# V0_1.net
KiCad netlist of a schematic drawn in EAGLE
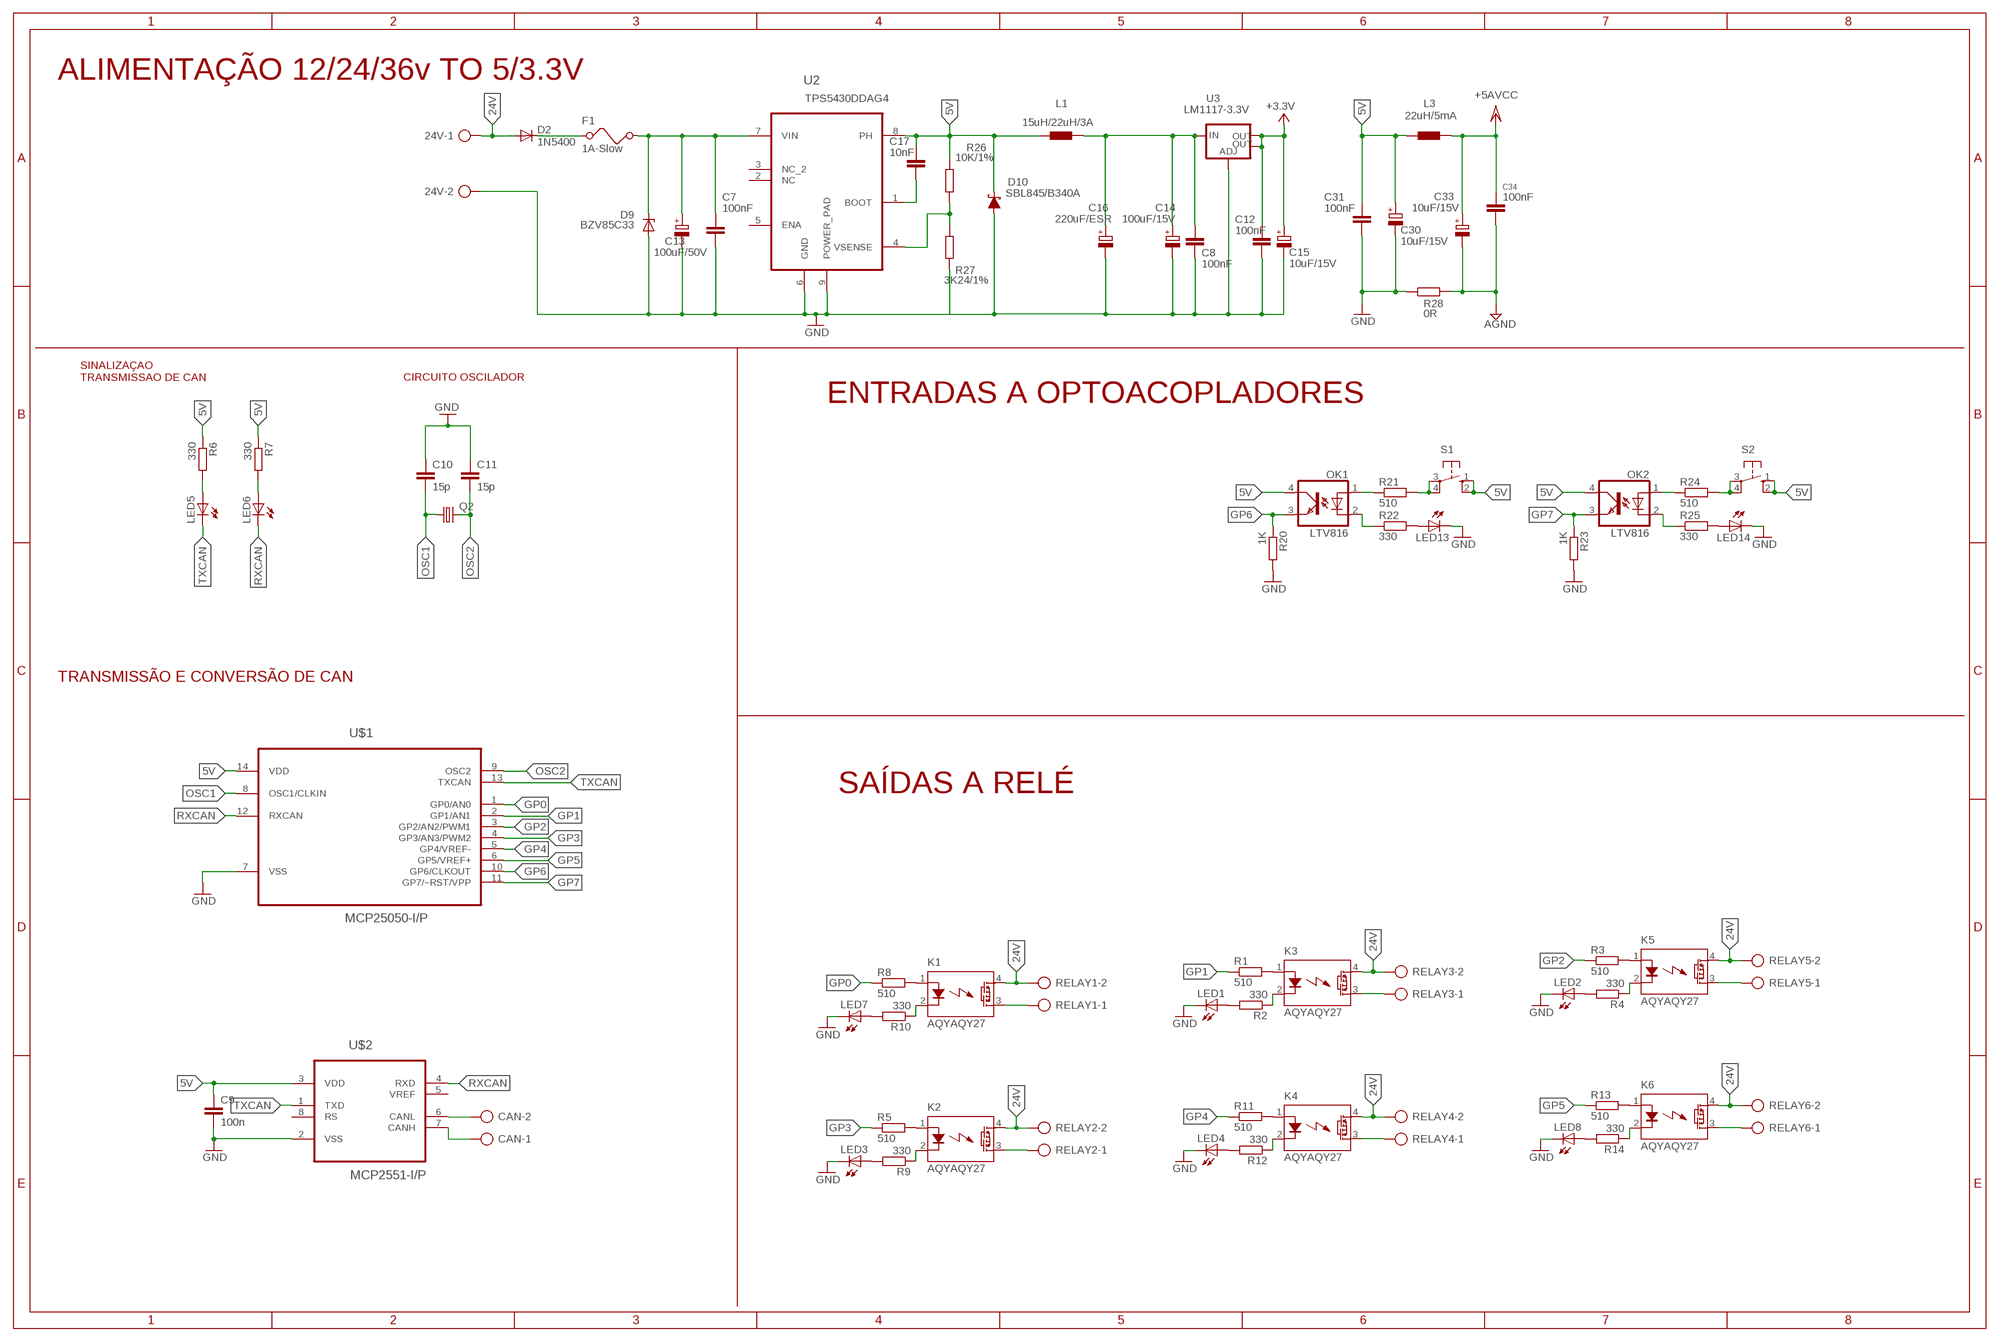
[diagram p0: schematic, sheet 1]

(export (version "E")
  (design (tool "Eeschema 10.0.6"))
  (components
    (comp (ref "24V")
      (value "AK300/2")
      (footprint "eagle-import:AK300_2")
      (libsource (lib "eagle-import") (part "AK300/2"))
    )
    (comp (ref "C7")
      (value "100nF")
      (footprint "eagle-import:C0805")
      (libsource (lib "eagle-import") (part "C-EUC0805"))
    )
    (comp (ref "C8")
      (value "100nF")
      (footprint "eagle-import:C0805")
      (libsource (lib "eagle-import") (part "C-EUC0805"))
    )
    (comp (ref "C9")
      (value "100n")
      (footprint "eagle-import:C050-025X075")
      (libsource (lib "eagle-import") (part "C-EU050-025X075"))
    )
    (comp (ref "C10")
      (value "15p")
      (footprint "eagle-import:C025-024X044")
      (libsource (lib "eagle-import") (part "C-EU025-024X044"))
    )
    (comp (ref "C11")
      (value "15p")
      (footprint "eagle-import:C025-024X044")
      (libsource (lib "eagle-import") (part "C-EU025-024X044"))
    )
    (comp (ref "C12")
      (value "100nF")
      (footprint "eagle-import:C0805")
      (libsource (lib "eagle-import") (part "C-EUC0805"))
    )
    (comp (ref "C13")
      (value "100uF/50V")
      (footprint "eagle-import:E5-10,5")
      (libsource (lib "eagle-import") (part "CPOL-EUE5-10.5"))
    )
    (comp (ref "C14")
      (value "100uF/15V")
      (footprint "eagle-import:E5-10,5")
      (libsource (lib "eagle-import") (part "CPOL-EUE5-10.5"))
    )
    (comp (ref "C15")
      (value "10uF/15V")
      (footprint "eagle-import:E5-10,5")
      (libsource (lib "eagle-import") (part "CPOL-EUE5-10.5"))
    )
    (comp (ref "C16")
      (value "220uF/ESR")
      (footprint "eagle-import:E5-10,5")
      (libsource (lib "eagle-import") (part "CPOL-EUE5-10.5"))
    )
    (comp (ref "C17")
      (value "10nF")
      (footprint "eagle-import:C0805")
      (libsource (lib "eagle-import") (part "C-EUC0805"))
    )
    (comp (ref "C30")
      (value "10uF/15V")
      (footprint "eagle-import:E5-10,5")
      (libsource (lib "eagle-import") (part "CPOL-EUE5-10.5"))
    )
    (comp (ref "C31")
      (value "100nF")
      (footprint "eagle-import:C0805")
      (libsource (lib "eagle-import") (part "C-EUC0805"))
    )
    (comp (ref "C33")
      (value "10uF/15V")
      (footprint "eagle-import:E5-10,5")
      (libsource (lib "eagle-import") (part "CPOL-EUE5-10.5"))
    )
    (comp (ref "C34")
      (value "100nF")
      (footprint "eagle-import:C0805")
      (libsource (lib "eagle-import") (part "C-EUC0805"))
    )
    (comp (ref "CAN")
      (value "AK300/2")
      (footprint "eagle-import:AK300_2")
      (libsource (lib "eagle-import") (part "AK300/2"))
    )
    (comp (ref "D2")
      (value "1N5400")
      (footprint "eagle-import:DO201-15")
      (libsource (lib "eagle-import") (part "1N5400"))
    )
    (comp (ref "D9")
      (value "BZV85C33")
      (footprint "eagle-import:F126Z10")
      (libsource (lib "eagle-import") (part "ZENER-DIODEF126-10"))
    )
    (comp (ref "D10")
      (value "SBL845/B340A")
      (footprint "eagle-import:SMA-DIODE")
      (libsource (lib "eagle-import") (part "DIODE-SCHOTTKY-B340A"))
    )
    (comp (ref "F1")
      (value "1A-Slow")
      (footprint "eagle-import:FUSE")
      (libsource (lib "eagle-import") (part "FUSE"))
    )
    (comp (ref "K1")
      (value "AQYAQY27")
      (footprint "eagle-import:AQY27")
      (libsource (lib "eagle-import") (part "AQYAQY27"))
    )
    (comp (ref "K2")
      (value "AQYAQY27")
      (footprint "eagle-import:AQY27")
      (libsource (lib "eagle-import") (part "AQYAQY27"))
    )
    (comp (ref "K3")
      (value "AQYAQY27")
      (footprint "eagle-import:AQY27")
      (libsource (lib "eagle-import") (part "AQYAQY27"))
    )
    (comp (ref "K4")
      (value "AQYAQY27")
      (footprint "eagle-import:AQY27")
      (libsource (lib "eagle-import") (part "AQYAQY27"))
    )
    (comp (ref "K5")
      (value "AQYAQY27")
      (footprint "eagle-import:AQY27")
      (libsource (lib "eagle-import") (part "AQYAQY27"))
    )
    (comp (ref "K6")
      (value "AQYAQY27")
      (footprint "eagle-import:AQY27")
      (libsource (lib "eagle-import") (part "AQYAQY27"))
    )
    (comp (ref "L1")
      (value "15uH/22uH/3A")
      (footprint "eagle-import:DR1030")
      (libsource (lib "eagle-import") (part "DR1030"))
    )
    (comp (ref "L3")
      (value "22uH/5mA")
      (footprint "eagle-import:BL01RN1A")
      (libsource (lib "eagle-import") (part "BL01RN1A"))
    )
    (comp (ref "LED1")
      (value "LED3MM")
      (footprint "eagle-import:LED3MM")
      (libsource (lib "eagle-import") (part "LED3MM"))
    )
    (comp (ref "LED2")
      (value "LED3MM")
      (footprint "eagle-import:LED3MM")
      (libsource (lib "eagle-import") (part "LED3MM"))
    )
    (comp (ref "LED3")
      (value "LED3MM")
      (footprint "eagle-import:LED3MM")
      (libsource (lib "eagle-import") (part "LED3MM"))
    )
    (comp (ref "LED4")
      (value "LED3MM")
      (footprint "eagle-import:LED3MM")
      (libsource (lib "eagle-import") (part "LED3MM"))
    )
    (comp (ref "LED5")
      (value "LED3MM")
      (footprint "eagle-import:LED3MM")
      (libsource (lib "eagle-import") (part "LED3MM"))
    )
    (comp (ref "LED6")
      (value "LED3MM")
      (footprint "eagle-import:LED3MM")
      (libsource (lib "eagle-import") (part "LED3MM"))
    )
    (comp (ref "LED7")
      (value "LED3MM")
      (footprint "eagle-import:LED3MM")
      (libsource (lib "eagle-import") (part "LED3MM"))
    )
    (comp (ref "LED8")
      (value "LED3MM")
      (footprint "eagle-import:LED3MM")
      (libsource (lib "eagle-import") (part "LED3MM"))
    )
    (comp (ref "LED13")
      (value "LED3MM")
      (footprint "eagle-import:LED3MM")
      (libsource (lib "eagle-import") (part "LED3MM"))
    )
    (comp (ref "LED14")
      (value "LED3MM")
      (footprint "eagle-import:LED3MM")
      (libsource (lib "eagle-import") (part "LED3MM"))
    )
    (comp (ref "OK1")
      (value "LTV816")
      (footprint "eagle-import:DIL04")
      (libsource (lib "eagle-import") (part "LTV816"))
    )
    (comp (ref "OK2")
      (value "LTV816")
      (footprint "eagle-import:DIL04")
      (libsource (lib "eagle-import") (part "LTV816"))
    )
    (comp (ref "Q2")
      (value "CRYSTALHC49S")
      (footprint "eagle-import:HC49_S")
      (libsource (lib "eagle-import") (part "CRYSTALHC49S"))
    )
    (comp (ref "R1")
      (value "510")
      (footprint "eagle-import:0204_5")
      (libsource (lib "eagle-import") (part "R-EU_0204/5"))
    )
    (comp (ref "R2")
      (value "330")
      (footprint "eagle-import:0204_5")
      (libsource (lib "eagle-import") (part "R-EU_0204/5"))
    )
    (comp (ref "R3")
      (value "510")
      (footprint "eagle-import:0204_5")
      (libsource (lib "eagle-import") (part "R-EU_0204/5"))
    )
    (comp (ref "R4")
      (value "330")
      (footprint "eagle-import:0204_5")
      (libsource (lib "eagle-import") (part "R-EU_0204/5"))
    )
    (comp (ref "R5")
      (value "510")
      (footprint "eagle-import:0204_5")
      (libsource (lib "eagle-import") (part "R-EU_0204/5"))
    )
    (comp (ref "R6")
      (value "330")
      (footprint "eagle-import:0204_5")
      (libsource (lib "eagle-import") (part "R-EU_0204/5"))
    )
    (comp (ref "R7")
      (value "330")
      (footprint "eagle-import:0204_5")
      (libsource (lib "eagle-import") (part "R-EU_0204/5"))
    )
    (comp (ref "R8")
      (value "510")
      (footprint "eagle-import:0204_5")
      (libsource (lib "eagle-import") (part "R-EU_0204/5"))
    )
    (comp (ref "R9")
      (value "330")
      (footprint "eagle-import:0204_5")
      (libsource (lib "eagle-import") (part "R-EU_0204/5"))
    )
    (comp (ref "R10")
      (value "330")
      (footprint "eagle-import:0204_5")
      (libsource (lib "eagle-import") (part "R-EU_0204/5"))
    )
    (comp (ref "R11")
      (value "510")
      (footprint "eagle-import:0204_5")
      (libsource (lib "eagle-import") (part "R-EU_0204/5"))
    )
    (comp (ref "R12")
      (value "330")
      (footprint "eagle-import:0204_5")
      (libsource (lib "eagle-import") (part "R-EU_0204/5"))
    )
    (comp (ref "R13")
      (value "510")
      (footprint "eagle-import:0204_5")
      (libsource (lib "eagle-import") (part "R-EU_0204/5"))
    )
    (comp (ref "R14")
      (value "330")
      (footprint "eagle-import:0204_5")
      (libsource (lib "eagle-import") (part "R-EU_0204/5"))
    )
    (comp (ref "R20")
      (value "1K")
      (footprint "eagle-import:0204_5")
      (libsource (lib "eagle-import") (part "R-EU_0204/5"))
    )
    (comp (ref "R21")
      (value "510")
      (footprint "eagle-import:0204_5")
      (libsource (lib "eagle-import") (part "R-EU_0204/5"))
    )
    (comp (ref "R22")
      (value "330")
      (footprint "eagle-import:0204_5")
      (libsource (lib "eagle-import") (part "R-EU_0204/5"))
    )
    (comp (ref "R23")
      (value "1K")
      (footprint "eagle-import:0204_5")
      (libsource (lib "eagle-import") (part "R-EU_0204/5"))
    )
    (comp (ref "R24")
      (value "510")
      (footprint "eagle-import:0204_5")
      (libsource (lib "eagle-import") (part "R-EU_0204/5"))
    )
    (comp (ref "R25")
      (value "330")
      (footprint "eagle-import:0204_5")
      (libsource (lib "eagle-import") (part "R-EU_0204/5"))
    )
    (comp (ref "R26")
      (value "10K/1%")
      (footprint "eagle-import:R0603")
      (libsource (lib "eagle-import") (part "R-EU_R0603"))
    )
    (comp (ref "R27")
      (value "3K24/1%")
      (footprint "eagle-import:R0603")
      (libsource (lib "eagle-import") (part "R-EU_R0603"))
    )
    (comp (ref "R28")
      (value "0R")
      (footprint "eagle-import:R0603")
      (libsource (lib "eagle-import") (part "R-EU_R0603"))
    )
    (comp (ref "RELAY1")
      (value "AK300/2")
      (footprint "eagle-import:AK300_2")
      (libsource (lib "eagle-import") (part "AK300/2"))
    )
    (comp (ref "RELAY2")
      (value "AK300/2")
      (footprint "eagle-import:AK300_2")
      (libsource (lib "eagle-import") (part "AK300/2"))
    )
    (comp (ref "RELAY3")
      (value "AK300/2")
      (footprint "eagle-import:AK300_2")
      (libsource (lib "eagle-import") (part "AK300/2"))
    )
    (comp (ref "RELAY4")
      (value "AK300/2")
      (footprint "eagle-import:AK300_2")
      (libsource (lib "eagle-import") (part "AK300/2"))
    )
    (comp (ref "RELAY5")
      (value "AK300/2")
      (footprint "eagle-import:AK300_2")
      (libsource (lib "eagle-import") (part "AK300/2"))
    )
    (comp (ref "RELAY6")
      (value "AK300/2")
      (footprint "eagle-import:AK300_2")
      (libsource (lib "eagle-import") (part "AK300/2"))
    )
    (comp (ref "S1")
      (value "10-XX")
      (footprint "eagle-import:B3F-10XX")
      (fields (field (name "MPN") "B3F-1000"))
      (libsource (lib "eagle-import") (part "10-XX"))
    )
    (comp (ref "S2")
      (value "10-XX")
      (footprint "eagle-import:B3F-10XX")
      (fields (field (name "MPN") "B3F-1000"))
      (libsource (lib "eagle-import") (part "10-XX"))
    )
    (comp (ref "U$1")
      (value "MCP25050-I/P")
      (footprint "eagle-import:DIP254P762X432-14")
      (libsource (lib "eagle-import") (part "MCP25050-I/P"))
    )
    (comp (ref "U$2")
      (value "MCP2551-I/P")
      (footprint "eagle-import:DIP254P762X432-8")
      (libsource (lib "eagle-import") (part "MCP2551-I/P"))
    )
    (comp (ref "U2")
      (value "TPS5430DDAG4")
      (footprint "eagle-import:SOIC127P600X170-9N")
      (fields (field (name "MPN") "TPS5430DDAG4"))
      (libsource (lib "eagle-import") (part "TPS5430DDAG4"))
    )
    (comp (ref "U3")
      (value "LM1117-3.3V")
      (footprint "eagle-import:SOT223")
      (libsource (lib "eagle-import") (part "V_REG_LM1117SOT223"))
    )
  )
  (nets
    (net (code "1") (name "+3.3V") (class "Default")
      (node (ref "C12") (pin "1") (pinfunction "1_1") (pintype "passive"))
      (node (ref "C15") (pin "+") (pinfunction "+_+") (pintype "passive"))
      (node (ref "U3") (pin "2") (pinfunction "OUT_2") (pintype "output"))
      (node (ref "U3") (pin "4") (pinfunction "OUT_4") (pintype "output"))
    )
    (net (code "2") (name "+5AVCC") (class "Default")
      (node (ref "C33") (pin "+") (pinfunction "+_+") (pintype "passive"))
      (node (ref "C34") (pin "1") (pinfunction "1_1") (pintype "passive"))
      (node (ref "L3") (pin "2") (pinfunction "2_2") (pintype "passive"))
    )
    (net (code "3") (name "5V") (class "Default")
      (node (ref "C17") (pin "1") (pinfunction "1_1") (pintype "passive"))
      (node (ref "C30") (pin "+") (pinfunction "+_+") (pintype "passive"))
      (node (ref "C31") (pin "1") (pinfunction "1_1") (pintype "passive"))
      (node (ref "C9") (pin "1") (pinfunction "1_1") (pintype "passive"))
      (node (ref "D10") (pin "C") (pinfunction "C_C") (pintype "passive"))
      (node (ref "L1") (pin "1") (pinfunction "1_1") (pintype "passive"))
      (node (ref "L3") (pin "1") (pinfunction "1_1") (pintype "passive"))
      (node (ref "OK1") (pin "4") (pinfunction "COL_4") (pintype "passive"))
      (node (ref "OK2") (pin "4") (pinfunction "COL_4") (pintype "passive"))
      (node (ref "R26") (pin "1") (pinfunction "1_1") (pintype "passive"))
      (node (ref "R6") (pin "1") (pinfunction "1_1") (pintype "passive"))
      (node (ref "R7") (pin "1") (pinfunction "1_1") (pintype "passive"))
      (node (ref "S1") (pin "1") (pinfunction "S_1") (pintype "passive"))
      (node (ref "S1") (pin "2") (pinfunction "S1_2") (pintype "passive"))
      (node (ref "S2") (pin "1") (pinfunction "S_1") (pintype "passive"))
      (node (ref "S2") (pin "2") (pinfunction "S1_2") (pintype "passive"))
      (node (ref "U$1") (pin "14") (pinfunction "VDD_14") (pintype "power_in"))
      (node (ref "U$2") (pin "3") (pinfunction "VDD_3") (pintype "power_in"))
      (node (ref "U2") (pin "8") (pinfunction "PH_8") (pintype "input"))
    )
    (net (code "4") (name "24V") (class "Default")
      (node (ref "24V") (pin "1") (pinfunction "KL_1") (pintype "passive"))
      (node (ref "D2") (pin "A") (pinfunction "A_A") (pintype "passive"))
      (node (ref "K1") (pin "4") (pinfunction "DS1_4") (pintype "passive"))
      (node (ref "K2") (pin "4") (pinfunction "DS1_4") (pintype "passive"))
      (node (ref "K3") (pin "4") (pinfunction "DS1_4") (pintype "passive"))
      (node (ref "K4") (pin "4") (pinfunction "DS1_4") (pintype "passive"))
      (node (ref "K5") (pin "4") (pinfunction "DS1_4") (pintype "passive"))
      (node (ref "K6") (pin "4") (pinfunction "DS1_4") (pintype "passive"))
      (node (ref "RELAY1") (pin "2") (pinfunction "KL_2") (pintype "passive"))
      (node (ref "RELAY2") (pin "2") (pinfunction "KL_2") (pintype "passive"))
      (node (ref "RELAY3") (pin "2") (pinfunction "KL_2") (pintype "passive"))
      (node (ref "RELAY4") (pin "2") (pinfunction "KL_2") (pintype "passive"))
      (node (ref "RELAY5") (pin "2") (pinfunction "KL_2") (pintype "passive"))
      (node (ref "RELAY6") (pin "2") (pinfunction "KL_2") (pintype "passive"))
    )
    (net (code "5") (name "AGND") (class "Default")
      (node (ref "C33") (pin "-") (pinfunction "-_-") (pintype "passive"))
      (node (ref "C34") (pin "2") (pinfunction "2_2") (pintype "passive"))
      (node (ref "R28") (pin "2") (pinfunction "2_2") (pintype "passive"))
    )
    (net (code "6") (name "GND") (class "Default")
      (node (ref "24V") (pin "2") (pinfunction "KL_2") (pintype "passive"))
      (node (ref "C10") (pin "1") (pinfunction "1_1") (pintype "passive"))
      (node (ref "C11") (pin "1") (pinfunction "1_1") (pintype "passive"))
      (node (ref "C12") (pin "2") (pinfunction "2_2") (pintype "passive"))
      (node (ref "C13") (pin "-") (pinfunction "-_-") (pintype "passive"))
      (node (ref "C14") (pin "-") (pinfunction "-_-") (pintype "passive"))
      (node (ref "C15") (pin "-") (pinfunction "-_-") (pintype "passive"))
      (node (ref "C16") (pin "-") (pinfunction "-_-") (pintype "passive"))
      (node (ref "C30") (pin "-") (pinfunction "-_-") (pintype "passive"))
      (node (ref "C31") (pin "2") (pinfunction "2_2") (pintype "passive"))
      (node (ref "C7") (pin "2") (pinfunction "2_2") (pintype "passive"))
      (node (ref "C8") (pin "2") (pinfunction "2_2") (pintype "passive"))
      (node (ref "C9") (pin "2") (pinfunction "2_2") (pintype "passive"))
      (node (ref "D10") (pin "A") (pinfunction "A_A") (pintype "passive"))
      (node (ref "D9") (pin "A") (pinfunction "A_A") (pintype "passive"))
      (node (ref "LED1") (pin "K") (pinfunction "C_K") (pintype "passive"))
      (node (ref "LED13") (pin "K") (pinfunction "C_K") (pintype "passive"))
      (node (ref "LED14") (pin "K") (pinfunction "C_K") (pintype "passive"))
      (node (ref "LED2") (pin "K") (pinfunction "C_K") (pintype "passive"))
      (node (ref "LED3") (pin "K") (pinfunction "C_K") (pintype "passive"))
      (node (ref "LED4") (pin "K") (pinfunction "C_K") (pintype "passive"))
      (node (ref "LED7") (pin "K") (pinfunction "C_K") (pintype "passive"))
      (node (ref "LED8") (pin "K") (pinfunction "C_K") (pintype "passive"))
      (node (ref "R20") (pin "2") (pinfunction "2_2") (pintype "passive"))
      (node (ref "R23") (pin "2") (pinfunction "2_2") (pintype "passive"))
      (node (ref "R27") (pin "2") (pinfunction "2_2") (pintype "passive"))
      (node (ref "R28") (pin "1") (pinfunction "1_1") (pintype "passive"))
      (node (ref "U$1") (pin "7") (pinfunction "VSS_7") (pintype "passive"))
      (node (ref "U$2") (pin "2") (pinfunction "VSS_2") (pintype "power_in"))
      (node (ref "U2") (pin "6") (pinfunction "GND_6") (pintype "passive"))
      (node (ref "U2") (pin "9") (pinfunction "POWER_PAD_9") (pintype "passive"))
      (node (ref "U3") (pin "1") (pinfunction "ADJ_1") (pintype "input"))
    )
    (net (code "7") (name "GP0") (class "Default")
      (node (ref "R8") (pin "1") (pinfunction "1_1") (pintype "passive"))
      (node (ref "U$1") (pin "1") (pinfunction "GP0/AN0_1") (pintype "bidirectional"))
    )
    (net (code "8") (name "GP1") (class "Default")
      (node (ref "R1") (pin "1") (pinfunction "1_1") (pintype "passive"))
      (node (ref "U$1") (pin "2") (pinfunction "GP1/AN1_2") (pintype "bidirectional"))
    )
    (net (code "9") (name "GP2") (class "Default")
      (node (ref "R3") (pin "1") (pinfunction "1_1") (pintype "passive"))
      (node (ref "U$1") (pin "3") (pinfunction "GP2/AN2/PWM1_3") (pintype "bidirectional"))
    )
    (net (code "10") (name "GP3") (class "Default")
      (node (ref "R5") (pin "1") (pinfunction "1_1") (pintype "passive"))
      (node (ref "U$1") (pin "4") (pinfunction "GP3/AN3/PWM2_4") (pintype "bidirectional"))
    )
    (net (code "11") (name "GP4") (class "Default")
      (node (ref "R11") (pin "1") (pinfunction "1_1") (pintype "passive"))
      (node (ref "U$1") (pin "5") (pinfunction "GP4/VREF-_5") (pintype "bidirectional"))
    )
    (net (code "12") (name "GP5") (class "Default")
      (node (ref "R13") (pin "1") (pinfunction "1_1") (pintype "passive"))
      (node (ref "U$1") (pin "6") (pinfunction "GP5/VREF+_6") (pintype "bidirectional"))
    )
    (net (code "13") (name "GP6") (class "Default")
      (node (ref "OK1") (pin "3") (pinfunction "EMIT_3") (pintype "passive"))
      (node (ref "R20") (pin "1") (pinfunction "1_1") (pintype "passive"))
      (node (ref "U$1") (pin "10") (pinfunction "GP6/CLKOUT_10") (pintype "bidirectional"))
    )
    (net (code "14") (name "GP7") (class "Default")
      (node (ref "OK2") (pin "3") (pinfunction "EMIT_3") (pintype "passive"))
      (node (ref "R23") (pin "1") (pinfunction "1_1") (pintype "passive"))
      (node (ref "U$1") (pin "11") (pinfunction "GP7/~{RST/VPP}_11") (pintype "bidirectional"))
    )
    (net (code "15") (name "Net-(CANA-KL)") (class "Default")
      (node (ref "CAN") (pin "1") (pinfunction "KL_1") (pintype "passive"))
      (node (ref "U$2") (pin "7") (pinfunction "CANH_7") (pintype "bidirectional"))
    )
    (net (code "16") (name "Net-(CANB-KL)") (class "Default")
      (node (ref "CAN") (pin "2") (pinfunction "KL_2") (pintype "passive"))
      (node (ref "U$2") (pin "6") (pinfunction "CANL_6") (pintype "bidirectional"))
    )
    (net (code "17") (name "Net-(D2-PadC)") (class "Default")
      (node (ref "D2") (pin "C") (pinfunction "C_C") (pintype "passive"))
      (node (ref "F1") (pin "1") (pinfunction "1_1") (pintype "passive"))
    )
    (net (code "18") (name "Net-(K1-A)") (class "Default")
      (node (ref "K1") (pin "1") (pinfunction "A_1") (pintype "passive"))
      (node (ref "R8") (pin "2") (pinfunction "2_2") (pintype "passive"))
    )
    (net (code "19") (name "Net-(K1-DS2)") (class "Default")
      (node (ref "K1") (pin "3") (pinfunction "DS2_3") (pintype "passive"))
      (node (ref "RELAY1") (pin "1") (pinfunction "KL_1") (pintype "passive"))
    )
    (net (code "20") (name "Net-(K1-K)") (class "Default")
      (node (ref "K1") (pin "2") (pinfunction "K_2") (pintype "passive"))
      (node (ref "R10") (pin "1") (pinfunction "1_1") (pintype "passive"))
    )
    (net (code "21") (name "Net-(K2-A)") (class "Default")
      (node (ref "K2") (pin "1") (pinfunction "A_1") (pintype "passive"))
      (node (ref "R5") (pin "2") (pinfunction "2_2") (pintype "passive"))
    )
    (net (code "22") (name "Net-(K2-DS2)") (class "Default")
      (node (ref "K2") (pin "3") (pinfunction "DS2_3") (pintype "passive"))
      (node (ref "RELAY2") (pin "1") (pinfunction "KL_1") (pintype "passive"))
    )
    (net (code "23") (name "Net-(K2-K)") (class "Default")
      (node (ref "K2") (pin "2") (pinfunction "K_2") (pintype "passive"))
      (node (ref "R9") (pin "1") (pinfunction "1_1") (pintype "passive"))
    )
    (net (code "24") (name "Net-(K3-A)") (class "Default")
      (node (ref "K3") (pin "1") (pinfunction "A_1") (pintype "passive"))
      (node (ref "R1") (pin "2") (pinfunction "2_2") (pintype "passive"))
    )
    (net (code "25") (name "Net-(K3-DS2)") (class "Default")
      (node (ref "K3") (pin "3") (pinfunction "DS2_3") (pintype "passive"))
      (node (ref "RELAY3") (pin "1") (pinfunction "KL_1") (pintype "passive"))
    )
    (net (code "26") (name "Net-(K3-K)") (class "Default")
      (node (ref "K3") (pin "2") (pinfunction "K_2") (pintype "passive"))
      (node (ref "R2") (pin "1") (pinfunction "1_1") (pintype "passive"))
    )
    (net (code "27") (name "Net-(K4-A)") (class "Default")
      (node (ref "K4") (pin "1") (pinfunction "A_1") (pintype "passive"))
      (node (ref "R11") (pin "2") (pinfunction "2_2") (pintype "passive"))
    )
    (net (code "28") (name "Net-(K4-DS2)") (class "Default")
      (node (ref "K4") (pin "3") (pinfunction "DS2_3") (pintype "passive"))
      (node (ref "RELAY4") (pin "1") (pinfunction "KL_1") (pintype "passive"))
    )
    (net (code "29") (name "Net-(K4-K)") (class "Default")
      (node (ref "K4") (pin "2") (pinfunction "K_2") (pintype "passive"))
      (node (ref "R12") (pin "1") (pinfunction "1_1") (pintype "passive"))
    )
    (net (code "30") (name "Net-(K5-A)") (class "Default")
      (node (ref "K5") (pin "1") (pinfunction "A_1") (pintype "passive"))
      (node (ref "R3") (pin "2") (pinfunction "2_2") (pintype "passive"))
    )
    (net (code "31") (name "Net-(K5-DS2)") (class "Default")
      (node (ref "K5") (pin "3") (pinfunction "DS2_3") (pintype "passive"))
      (node (ref "RELAY5") (pin "1") (pinfunction "KL_1") (pintype "passive"))
    )
    (net (code "32") (name "Net-(K5-K)") (class "Default")
      (node (ref "K5") (pin "2") (pinfunction "K_2") (pintype "passive"))
      (node (ref "R4") (pin "1") (pinfunction "1_1") (pintype "passive"))
    )
    (net (code "33") (name "Net-(K6-A)") (class "Default")
      (node (ref "K6") (pin "1") (pinfunction "A_1") (pintype "passive"))
      (node (ref "R13") (pin "2") (pinfunction "2_2") (pintype "passive"))
    )
    (net (code "34") (name "Net-(K6-DS2)") (class "Default")
      (node (ref "K6") (pin "3") (pinfunction "DS2_3") (pintype "passive"))
      (node (ref "RELAY6") (pin "1") (pinfunction "KL_1") (pintype "passive"))
    )
    (net (code "35") (name "Net-(K6-K)") (class "Default")
      (node (ref "K6") (pin "2") (pinfunction "K_2") (pintype "passive"))
      (node (ref "R14") (pin "1") (pinfunction "1_1") (pintype "passive"))
    )
    (net (code "36") (name "Net-(LED1-PadA)") (class "Default")
      (node (ref "LED1") (pin "A") (pinfunction "A_A") (pintype "passive"))
      (node (ref "R2") (pin "2") (pinfunction "2_2") (pintype "passive"))
    )
    (net (code "37") (name "Net-(LED2-PadA)") (class "Default")
      (node (ref "LED2") (pin "A") (pinfunction "A_A") (pintype "passive"))
      (node (ref "R4") (pin "2") (pinfunction "2_2") (pintype "passive"))
    )
    (net (code "38") (name "Net-(LED3-PadA)") (class "Default")
      (node (ref "LED3") (pin "A") (pinfunction "A_A") (pintype "passive"))
      (node (ref "R9") (pin "2") (pinfunction "2_2") (pintype "passive"))
    )
    (net (code "39") (name "Net-(LED4-PadA)") (class "Default")
      (node (ref "LED4") (pin "A") (pinfunction "A_A") (pintype "passive"))
      (node (ref "R12") (pin "2") (pinfunction "2_2") (pintype "passive"))
    )
    (net (code "40") (name "Net-(LED5-PadA)") (class "Default")
      (node (ref "LED5") (pin "A") (pinfunction "A_A") (pintype "passive"))
      (node (ref "R6") (pin "2") (pinfunction "2_2") (pintype "passive"))
    )
    (net (code "41") (name "Net-(LED6-PadA)") (class "Default")
      (node (ref "LED6") (pin "A") (pinfunction "A_A") (pintype "passive"))
      (node (ref "R7") (pin "2") (pinfunction "2_2") (pintype "passive"))
    )
    (net (code "42") (name "Net-(LED7-PadA)") (class "Default")
      (node (ref "LED7") (pin "A") (pinfunction "A_A") (pintype "passive"))
      (node (ref "R10") (pin "2") (pinfunction "2_2") (pintype "passive"))
    )
    (net (code "43") (name "Net-(LED8-PadA)") (class "Default")
      (node (ref "LED8") (pin "A") (pinfunction "A_A") (pintype "passive"))
      (node (ref "R14") (pin "2") (pinfunction "2_2") (pintype "passive"))
    )
    (net (code "44") (name "Net-(LED13-PadA)") (class "Default")
      (node (ref "LED13") (pin "A") (pinfunction "A_A") (pintype "passive"))
      (node (ref "R22") (pin "2") (pinfunction "2_2") (pintype "passive"))
    )
    (net (code "45") (name "Net-(LED14-PadA)") (class "Default")
      (node (ref "LED14") (pin "A") (pinfunction "A_A") (pintype "passive"))
      (node (ref "R25") (pin "2") (pinfunction "2_2") (pintype "passive"))
    )
    (net (code "46") (name "Net-(OK1-A)") (class "Default")
      (node (ref "OK1") (pin "1") (pinfunction "A_1") (pintype "passive"))
      (node (ref "R21") (pin "1") (pinfunction "1_1") (pintype "passive"))
    )
    (net (code "47") (name "Net-(OK1-C)") (class "Default")
      (node (ref "OK1") (pin "2") (pinfunction "C_2") (pintype "passive"))
      (node (ref "R22") (pin "1") (pinfunction "1_1") (pintype "passive"))
    )
    (net (code "48") (name "Net-(OK2-A)") (class "Default")
      (node (ref "OK2") (pin "1") (pinfunction "A_1") (pintype "passive"))
      (node (ref "R24") (pin "1") (pinfunction "1_1") (pintype "passive"))
    )
    (net (code "49") (name "Net-(OK2-C)") (class "Default")
      (node (ref "OK2") (pin "2") (pinfunction "C_2") (pintype "passive"))
      (node (ref "R25") (pin "1") (pinfunction "1_1") (pintype "passive"))
    )
    (net (code "50") (name "Net-(S1-P)") (class "Default")
      (node (ref "R21") (pin "2") (pinfunction "2_2") (pintype "passive"))
      (node (ref "S1") (pin "3") (pinfunction "P_3") (pintype "passive"))
      (node (ref "S1") (pin "4") (pinfunction "P1_4") (pintype "passive"))
    )
    (net (code "51") (name "Net-(S2-P)") (class "Default")
      (node (ref "R24") (pin "2") (pinfunction "2_2") (pintype "passive"))
      (node (ref "S2") (pin "3") (pinfunction "P_3") (pintype "passive"))
      (node (ref "S2") (pin "4") (pinfunction "P1_4") (pintype "passive"))
    )
    (net (code "52") (name "Net-(U2-BOOT)") (class "Default")
      (node (ref "C17") (pin "2") (pinfunction "2_2") (pintype "passive"))
      (node (ref "U2") (pin "1") (pinfunction "BOOT_1") (pintype "passive"))
    )
    (net (code "53") (name "Net-(U2-VIN)") (class "Default")
      (node (ref "C13") (pin "+") (pinfunction "+_+") (pintype "passive"))
      (node (ref "C7") (pin "1") (pinfunction "1_1") (pintype "passive"))
      (node (ref "D9") (pin "C") (pinfunction "C_C") (pintype "passive"))
      (node (ref "F1") (pin "2") (pinfunction "2_2") (pintype "passive"))
      (node (ref "U2") (pin "7") (pinfunction "VIN_7") (pintype "power_in"))
    )
    (net (code "54") (name "Net-(U2-VSENSE)") (class "Default")
      (node (ref "R26") (pin "2") (pinfunction "2_2") (pintype "passive"))
      (node (ref "R27") (pin "1") (pinfunction "1_1") (pintype "passive"))
      (node (ref "U2") (pin "4") (pinfunction "VSENSE_4") (pintype "output"))
    )
    (net (code "55") (name "Net-(U3-IN)") (class "Default")
      (node (ref "C14") (pin "+") (pinfunction "+_+") (pintype "passive"))
      (node (ref "C16") (pin "+") (pinfunction "+_+") (pintype "passive"))
      (node (ref "C8") (pin "1") (pinfunction "1_1") (pintype "passive"))
      (node (ref "L1") (pin "2") (pinfunction "2_2") (pintype "passive"))
      (node (ref "U3") (pin "3") (pinfunction "IN_3") (pintype "input"))
    )
    (net (code "56") (name "OSC1") (class "Default")
      (node (ref "C10") (pin "2") (pinfunction "2_2") (pintype "passive"))
      (node (ref "Q2") (pin "1") (pinfunction "1_1") (pintype "passive"))
      (node (ref "U$1") (pin "8") (pinfunction "OSC1/CLKIN_8") (pintype "input"))
    )
    (net (code "57") (name "OSC2") (class "Default")
      (node (ref "C11") (pin "2") (pinfunction "2_2") (pintype "passive"))
      (node (ref "Q2") (pin "2") (pinfunction "2_2") (pintype "passive"))
      (node (ref "U$1") (pin "9") (pinfunction "OSC2_9") (pintype "output"))
    )
    (net (code "58") (name "RXCAN") (class "Default")
      (node (ref "LED6") (pin "K") (pinfunction "C_K") (pintype "passive"))
      (node (ref "U$1") (pin "12") (pinfunction "RXCAN_12") (pintype "input"))
      (node (ref "U$2") (pin "4") (pinfunction "RXD_4") (pintype "output"))
    )
    (net (code "59") (name "TXCAN") (class "Default")
      (node (ref "LED5") (pin "K") (pinfunction "C_K") (pintype "passive"))
      (node (ref "U$1") (pin "13") (pinfunction "TXCAN_13") (pintype "output"))
      (node (ref "U$2") (pin "1") (pinfunction "TXD_1") (pintype "input"))
    )
    (net (code "60") (name "unconnected-(U$2-RS-Pad8)") (class "Default")
      (node (ref "U$2") (pin "8") (pinfunction "RS_8") (pintype "input"))
    )
    (net (code "61") (name "unconnected-(U$2-VREF-Pad5)") (class "Default")
      (node (ref "U$2") (pin "5") (pinfunction "VREF_5") (pintype "output"))
    )
    (net (code "62") (name "unconnected-(U2-ENA-Pad5)") (class "Default")
      (node (ref "U2") (pin "5") (pinfunction "ENA_5") (pintype "input"))
    )
    (net (code "63") (name "unconnected-(U2-NC-Pad2)") (class "Default")
      (node (ref "U2") (pin "2") (pinfunction "NC_2") (pintype "no_connect"))
    )
    (net (code "64") (name "unconnected-(U2-NC_2-Pad3)") (class "Default")
      (node (ref "U2") (pin "3") (pinfunction "NC_2_3") (pintype "no_connect"))
    )
  )
)
